# vca.net
KiCad netlist of a schematic drawn in EAGLE
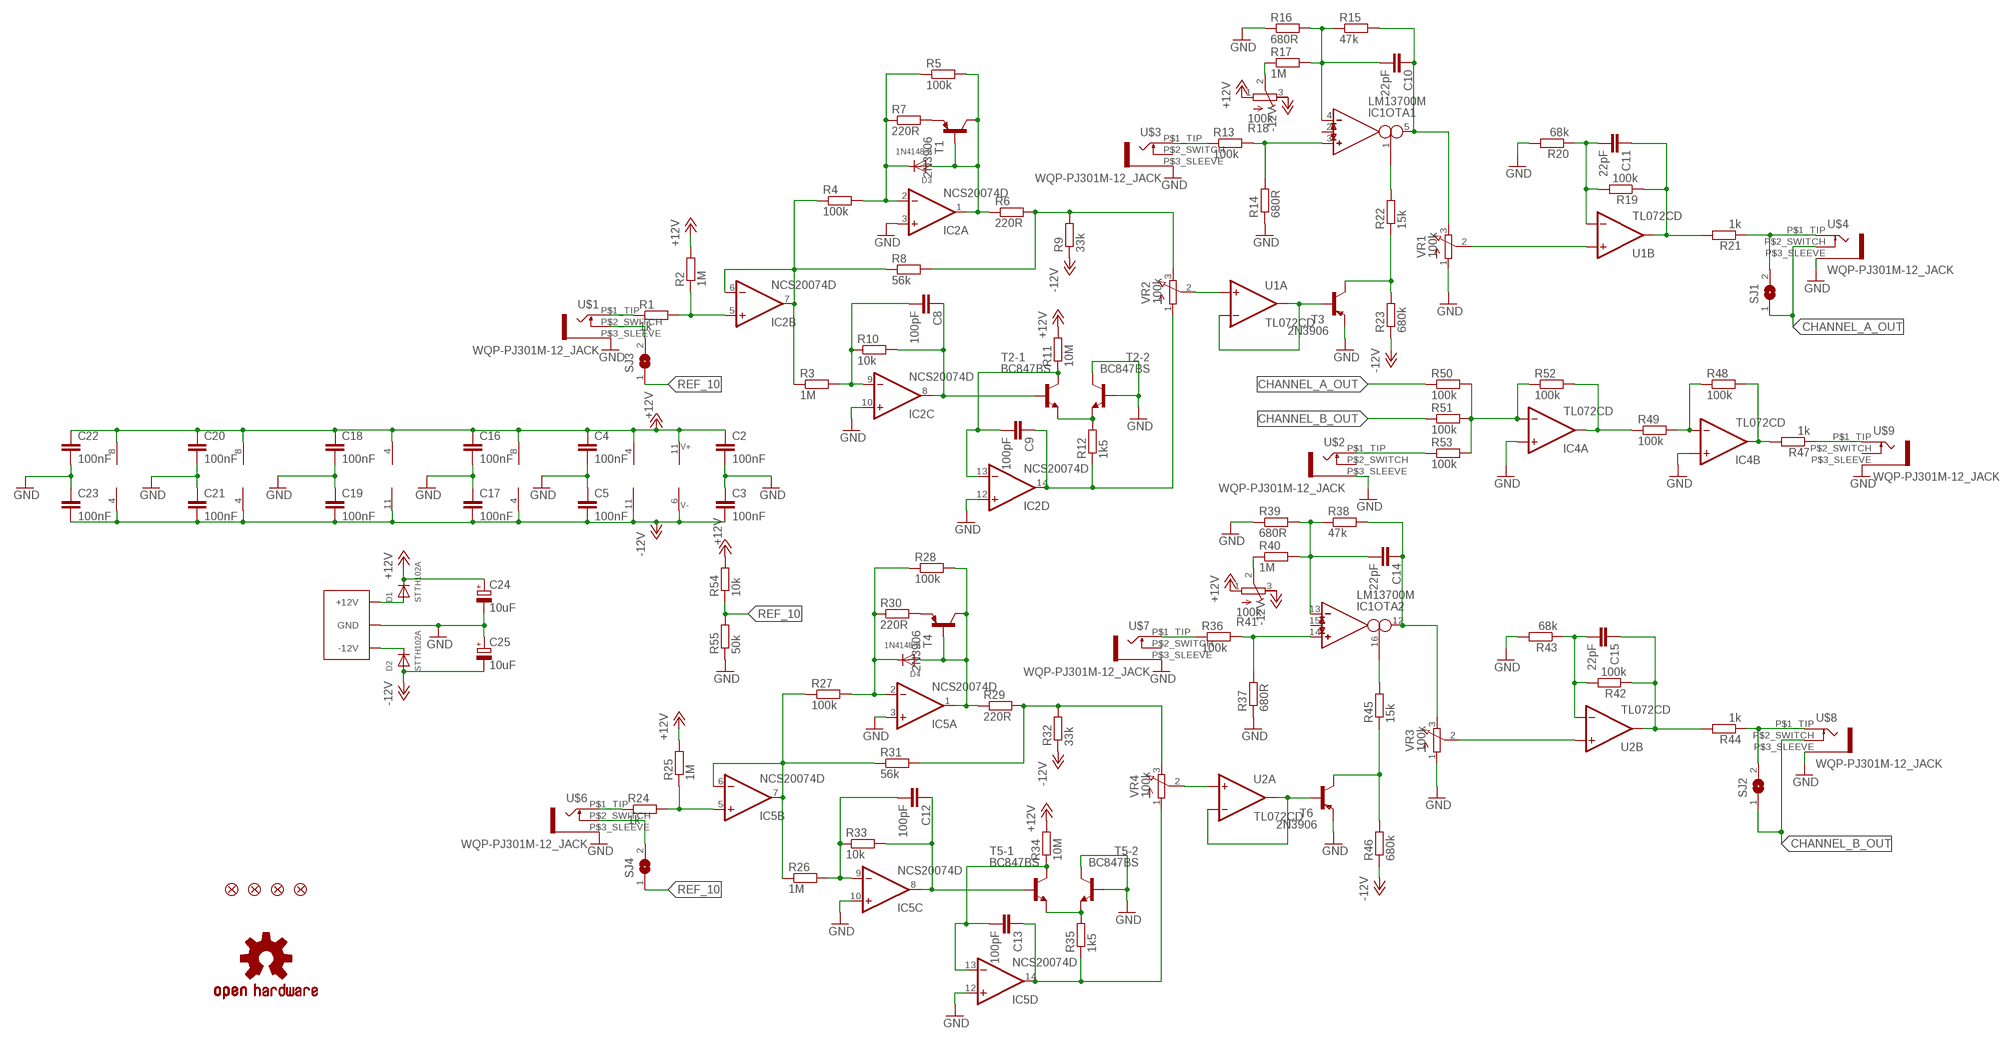
[diagram p0: schematic, sheet 1]

(export (version "E")
  (design (tool "Eeschema 10.0.6"))
  (components
    (comp (ref "C1")
      (value "EURO_POWER_LOCKFAT-LOCK")
      (footprint "eagle-import:EURO_PWR_HEADER_LOCK")
      (libsource (lib "eagle-import") (part "EURO_POWER_LOCKFAT-LOCK"))
    )
    (comp (ref "C2")
      (value "100nF")
      (footprint "eagle-import:C0402")
      (libsource (lib "eagle-import") (part "C-EUC0402"))
    )
    (comp (ref "C3")
      (value "100nF")
      (footprint "eagle-import:C0402")
      (libsource (lib "eagle-import") (part "C-EUC0402"))
    )
    (comp (ref "C4")
      (value "100nF")
      (footprint "eagle-import:C0402")
      (libsource (lib "eagle-import") (part "C-EUC0402"))
    )
    (comp (ref "C5")
      (value "100nF")
      (footprint "eagle-import:C0402")
      (libsource (lib "eagle-import") (part "C-EUC0402"))
    )
    (comp (ref "C8")
      (value "100pF")
      (footprint "eagle-import:C0402")
      (libsource (lib "eagle-import") (part "C-EUC0402"))
    )
    (comp (ref "C9")
      (value "100pF")
      (footprint "eagle-import:C0402")
      (libsource (lib "eagle-import") (part "C-EUC0402"))
    )
    (comp (ref "C10")
      (value "22pF")
      (footprint "eagle-import:C0402")
      (libsource (lib "eagle-import") (part "C-EUC0402"))
    )
    (comp (ref "C11")
      (value "22pF")
      (footprint "eagle-import:C0402")
      (libsource (lib "eagle-import") (part "C-EUC0402"))
    )
    (comp (ref "C12")
      (value "100pF")
      (footprint "eagle-import:C0402")
      (libsource (lib "eagle-import") (part "C-EUC0402"))
    )
    (comp (ref "C13")
      (value "100pF")
      (footprint "eagle-import:C0402")
      (libsource (lib "eagle-import") (part "C-EUC0402"))
    )
    (comp (ref "C14")
      (value "22pF")
      (footprint "eagle-import:C0402")
      (libsource (lib "eagle-import") (part "C-EUC0402"))
    )
    (comp (ref "C15")
      (value "22pF")
      (footprint "eagle-import:C0402")
      (libsource (lib "eagle-import") (part "C-EUC0402"))
    )
    (comp (ref "C16")
      (value "100nF")
      (footprint "eagle-import:C0402")
      (libsource (lib "eagle-import") (part "C-EUC0402"))
    )
    (comp (ref "C17")
      (value "100nF")
      (footprint "eagle-import:C0402")
      (libsource (lib "eagle-import") (part "C-EUC0402"))
    )
    (comp (ref "C18")
      (value "100nF")
      (footprint "eagle-import:C0402")
      (libsource (lib "eagle-import") (part "C-EUC0402"))
    )
    (comp (ref "C19")
      (value "100nF")
      (footprint "eagle-import:C0402")
      (libsource (lib "eagle-import") (part "C-EUC0402"))
    )
    (comp (ref "C20")
      (value "100nF")
      (footprint "eagle-import:C0402")
      (libsource (lib "eagle-import") (part "C-EUC0402"))
    )
    (comp (ref "C21")
      (value "100nF")
      (footprint "eagle-import:C0402")
      (libsource (lib "eagle-import") (part "C-EUC0402"))
    )
    (comp (ref "C22")
      (value "100nF")
      (footprint "eagle-import:C0402")
      (libsource (lib "eagle-import") (part "C-EUC0402"))
    )
    (comp (ref "C23")
      (value "100nF")
      (footprint "eagle-import:C0402")
      (libsource (lib "eagle-import") (part "C-EUC0402"))
    )
    (comp (ref "C24")
      (value "10uF")
      (footprint "eagle-import:A_3216-18W")
      (libsource (lib "eagle-import") (part "CPOL-EUA/3216-18W"))
    )
    (comp (ref "C25")
      (value "10uF")
      (footprint "eagle-import:A_3216-18W")
      (libsource (lib "eagle-import") (part "CPOL-EUA/3216-18W"))
    )
    (comp (ref "D1")
      (value "STTH102A")
      (footprint "eagle-import:SMADIODE")
      (libsource (lib "eagle-import") (part "DIODESMA"))
    )
    (comp (ref "D2")
      (value "STTH102A")
      (footprint "eagle-import:SMADIODE")
      (libsource (lib "eagle-import") (part "DIODESMA"))
    )
    (comp (ref "D3")
      (value "1N4148-2")
      (footprint "eagle-import:SOD-123")
      (libsource (lib "eagle-import") (part "DIODESOD-123"))
    )
    (comp (ref "D4")
      (value "1N4148-2")
      (footprint "eagle-import:SOD-123")
      (libsource (lib "eagle-import") (part "DIODESOD-123"))
    )
    (comp (ref "FD1")
      (value "FIDUCIAL1X2")
      (footprint "eagle-import:FIDUCIAL-1X2")
      (libsource (lib "eagle-import") (part "FIDUCIAL1X2"))
    )
    (comp (ref "FD2")
      (value "FIDUCIAL1X2")
      (footprint "eagle-import:FIDUCIAL-1X2")
      (libsource (lib "eagle-import") (part "FIDUCIAL1X2"))
    )
    (comp (ref "FD3")
      (value "FIDUCIAL1X2")
      (footprint "eagle-import:FIDUCIAL-1X2")
      (libsource (lib "eagle-import") (part "FIDUCIAL1X2"))
    )
    (comp (ref "FD4")
      (value "FIDUCIAL1X2")
      (footprint "eagle-import:FIDUCIAL-1X2")
      (libsource (lib "eagle-import") (part "FIDUCIAL1X2"))
    )
    (comp (ref "IC1")
      (value "LM13700M")
      (footprint "eagle-import:SO16")
      (libsource (lib "eagle-import") (part "LM13700M"))
    )
    (comp (ref "IC2")
      (value "NCS20074D")
      (footprint "eagle-import:SO14")
      (libsource (lib "eagle-import") (part "NCS20074D"))
    )
    (comp (ref "IC4")
      (value "TL072CD")
      (footprint "eagle-import:SOIC8")
      (libsource (lib "eagle-import") (part "TL072DC"))
    )
    (comp (ref "IC5")
      (value "NCS20074D")
      (footprint "eagle-import:SO14")
      (libsource (lib "eagle-import") (part "NCS20074D"))
    )
    (comp (ref "LOGO1")
      (value "OSHW-LOGOM")
      (footprint "eagle-import:OSHW-LOGO-M")
      (libsource (lib "eagle-import") (part "OSHW-LOGOM"))
    )
    (comp (ref "R1")
      (value "1k")
      (footprint "eagle-import:R0402")
      (libsource (lib "eagle-import") (part "R-EU_R0402"))
    )
    (comp (ref "R2")
      (value "1M")
      (footprint "eagle-import:R0402")
      (libsource (lib "eagle-import") (part "R-EU_R0402"))
    )
    (comp (ref "R3")
      (value "1M")
      (footprint "eagle-import:R0402")
      (libsource (lib "eagle-import") (part "R-EU_R0402"))
    )
    (comp (ref "R4")
      (value "100k")
      (footprint "eagle-import:R0402")
      (libsource (lib "eagle-import") (part "R-EU_R0402"))
    )
    (comp (ref "R5")
      (value "100k")
      (footprint "eagle-import:R0402")
      (libsource (lib "eagle-import") (part "R-EU_R0402"))
    )
    (comp (ref "R6")
      (value "220R")
      (footprint "eagle-import:R0402")
      (libsource (lib "eagle-import") (part "R-EU_R0402"))
    )
    (comp (ref "R7")
      (value "220R")
      (footprint "eagle-import:R0402")
      (libsource (lib "eagle-import") (part "R-EU_R0402"))
    )
    (comp (ref "R8")
      (value "56k")
      (footprint "eagle-import:R0402")
      (libsource (lib "eagle-import") (part "R-EU_R0402"))
    )
    (comp (ref "R9")
      (value "33k")
      (footprint "eagle-import:R0402")
      (libsource (lib "eagle-import") (part "R-EU_R0402"))
    )
    (comp (ref "R10")
      (value "10k")
      (footprint "eagle-import:R0402")
      (libsource (lib "eagle-import") (part "R-EU_R0402"))
    )
    (comp (ref "R11")
      (value "10M")
      (footprint "eagle-import:R0402")
      (libsource (lib "eagle-import") (part "R-EU_R0402"))
    )
    (comp (ref "R12")
      (value "1k5")
      (footprint "eagle-import:R0402")
      (libsource (lib "eagle-import") (part "R-EU_R0402"))
    )
    (comp (ref "R13")
      (value "100k")
      (footprint "eagle-import:R0402")
      (libsource (lib "eagle-import") (part "R-EU_R0402"))
    )
    (comp (ref "R14")
      (value "680R")
      (footprint "eagle-import:R0402")
      (libsource (lib "eagle-import") (part "R-EU_R0402"))
    )
    (comp (ref "R15")
      (value "47k")
      (footprint "eagle-import:R0402")
      (libsource (lib "eagle-import") (part "R-EU_R0402"))
    )
    (comp (ref "R16")
      (value "680R")
      (footprint "eagle-import:R0402")
      (libsource (lib "eagle-import") (part "R-EU_R0402"))
    )
    (comp (ref "R17")
      (value "1M")
      (footprint "eagle-import:R0402")
      (libsource (lib "eagle-import") (part "R-EU_R0402"))
    )
    (comp (ref "R18")
      (value "100k")
      (footprint "eagle-import:RTRIM64W")
      (libsource (lib "eagle-import") (part "R-TRIMM64W"))
    )
    (comp (ref "R19")
      (value "100k")
      (footprint "eagle-import:R0402")
      (libsource (lib "eagle-import") (part "R-EU_R0402"))
    )
    (comp (ref "R20")
      (value "68k")
      (footprint "eagle-import:R0402")
      (libsource (lib "eagle-import") (part "R-EU_R0402"))
    )
    (comp (ref "R21")
      (value "1k")
      (footprint "eagle-import:R0402")
      (libsource (lib "eagle-import") (part "R-EU_R0402"))
    )
    (comp (ref "R22")
      (value "15k")
      (footprint "eagle-import:R0402")
      (libsource (lib "eagle-import") (part "R-EU_R0402"))
    )
    (comp (ref "R23")
      (value "680k")
      (footprint "eagle-import:R0402")
      (libsource (lib "eagle-import") (part "R-EU_R0402"))
    )
    (comp (ref "R24")
      (value "1k")
      (footprint "eagle-import:R0402")
      (libsource (lib "eagle-import") (part "R-EU_R0402"))
    )
    (comp (ref "R25")
      (value "1M")
      (footprint "eagle-import:R0402")
      (libsource (lib "eagle-import") (part "R-EU_R0402"))
    )
    (comp (ref "R26")
      (value "1M")
      (footprint "eagle-import:R0402")
      (libsource (lib "eagle-import") (part "R-EU_R0402"))
    )
    (comp (ref "R27")
      (value "100k")
      (footprint "eagle-import:R0402")
      (libsource (lib "eagle-import") (part "R-EU_R0402"))
    )
    (comp (ref "R28")
      (value "100k")
      (footprint "eagle-import:R0402")
      (libsource (lib "eagle-import") (part "R-EU_R0402"))
    )
    (comp (ref "R29")
      (value "220R")
      (footprint "eagle-import:R0402")
      (libsource (lib "eagle-import") (part "R-EU_R0402"))
    )
    (comp (ref "R30")
      (value "220R")
      (footprint "eagle-import:R0402")
      (libsource (lib "eagle-import") (part "R-EU_R0402"))
    )
    (comp (ref "R31")
      (value "56k")
      (footprint "eagle-import:R0402")
      (libsource (lib "eagle-import") (part "R-EU_R0402"))
    )
    (comp (ref "R32")
      (value "33k")
      (footprint "eagle-import:R0402")
      (libsource (lib "eagle-import") (part "R-EU_R0402"))
    )
    (comp (ref "R33")
      (value "10k")
      (footprint "eagle-import:R0402")
      (libsource (lib "eagle-import") (part "R-EU_R0402"))
    )
    (comp (ref "R34")
      (value "10M")
      (footprint "eagle-import:R0402")
      (libsource (lib "eagle-import") (part "R-EU_R0402"))
    )
    (comp (ref "R35")
      (value "1k5")
      (footprint "eagle-import:R0402")
      (libsource (lib "eagle-import") (part "R-EU_R0402"))
    )
    (comp (ref "R36")
      (value "100k")
      (footprint "eagle-import:R0402")
      (libsource (lib "eagle-import") (part "R-EU_R0402"))
    )
    (comp (ref "R37")
      (value "680R")
      (footprint "eagle-import:R0402")
      (libsource (lib "eagle-import") (part "R-EU_R0402"))
    )
    (comp (ref "R38")
      (value "47k")
      (footprint "eagle-import:R0402")
      (libsource (lib "eagle-import") (part "R-EU_R0402"))
    )
    (comp (ref "R39")
      (value "680R")
      (footprint "eagle-import:R0402")
      (libsource (lib "eagle-import") (part "R-EU_R0402"))
    )
    (comp (ref "R40")
      (value "1M")
      (footprint "eagle-import:R0402")
      (libsource (lib "eagle-import") (part "R-EU_R0402"))
    )
    (comp (ref "R41")
      (value "100k")
      (footprint "eagle-import:RTRIM64W")
      (libsource (lib "eagle-import") (part "R-TRIMM64W"))
    )
    (comp (ref "R42")
      (value "100k")
      (footprint "eagle-import:R0402")
      (libsource (lib "eagle-import") (part "R-EU_R0402"))
    )
    (comp (ref "R43")
      (value "68k")
      (footprint "eagle-import:R0402")
      (libsource (lib "eagle-import") (part "R-EU_R0402"))
    )
    (comp (ref "R44")
      (value "1k")
      (footprint "eagle-import:R0402")
      (libsource (lib "eagle-import") (part "R-EU_R0402"))
    )
    (comp (ref "R45")
      (value "15k")
      (footprint "eagle-import:R0402")
      (libsource (lib "eagle-import") (part "R-EU_R0402"))
    )
    (comp (ref "R46")
      (value "680k")
      (footprint "eagle-import:R0402")
      (libsource (lib "eagle-import") (part "R-EU_R0402"))
    )
    (comp (ref "R47")
      (value "1k")
      (footprint "eagle-import:R0402")
      (libsource (lib "eagle-import") (part "R-EU_R0402"))
    )
    (comp (ref "R48")
      (value "100k")
      (footprint "eagle-import:R0402")
      (libsource (lib "eagle-import") (part "R-EU_R0402"))
    )
    (comp (ref "R49")
      (value "100k")
      (footprint "eagle-import:R0402")
      (libsource (lib "eagle-import") (part "R-EU_R0402"))
    )
    (comp (ref "R50")
      (value "100k")
      (footprint "eagle-import:R0402")
      (libsource (lib "eagle-import") (part "R-EU_R0402"))
    )
    (comp (ref "R51")
      (value "100k")
      (footprint "eagle-import:R0402")
      (libsource (lib "eagle-import") (part "R-EU_R0402"))
    )
    (comp (ref "R52")
      (value "100k")
      (footprint "eagle-import:R0402")
      (libsource (lib "eagle-import") (part "R-EU_R0402"))
    )
    (comp (ref "R53")
      (value "100k")
      (footprint "eagle-import:R0402")
      (libsource (lib "eagle-import") (part "R-EU_R0402"))
    )
    (comp (ref "R54")
      (value "10k")
      (footprint "eagle-import:R0402")
      (libsource (lib "eagle-import") (part "R-EU_R0402"))
    )
    (comp (ref "R55")
      (value "50k")
      (footprint "eagle-import:R0402")
      (libsource (lib "eagle-import") (part "R-EU_R0402"))
    )
    (comp (ref "SJ1") (value "SJ") (footprint "eagle-import:SJ") (libsource (lib "eagle-import") (part "SJ")))
    (comp (ref "SJ2") (value "SJ") (footprint "eagle-import:SJ") (libsource (lib "eagle-import") (part "SJ")))
    (comp (ref "SJ3") (value "SJ") (footprint "eagle-import:SJ") (libsource (lib "eagle-import") (part "SJ")))
    (comp (ref "SJ4") (value "SJ") (footprint "eagle-import:SJ") (libsource (lib "eagle-import") (part "SJ")))
    (comp (ref "T1")
      (value "2N3906")
      (footprint "eagle-import:SOT23-BEC")
      (libsource (lib "eagle-import") (part "-PNP-SOT23-BECMMBT3906LT1"))
    )
    (comp (ref "T2")
      (value "BC847BS")
      (footprint "eagle-import:SOT363")
      (libsource (lib "eagle-import") (part "BC847BS"))
    )
    (comp (ref "T3")
      (value "2N3906")
      (footprint "eagle-import:SOT23-BEC")
      (libsource (lib "eagle-import") (part "-PNP-SOT23-BECMMBT3906LT1"))
    )
    (comp (ref "T4")
      (value "2N3906")
      (footprint "eagle-import:SOT23-BEC")
      (libsource (lib "eagle-import") (part "-PNP-SOT23-BECMMBT3906LT1"))
    )
    (comp (ref "T5")
      (value "BC847BS")
      (footprint "eagle-import:SOT363")
      (libsource (lib "eagle-import") (part "BC847BS"))
    )
    (comp (ref "T6")
      (value "2N3906")
      (footprint "eagle-import:SOT23-BEC")
      (libsource (lib "eagle-import") (part "-PNP-SOT23-BECMMBT3906LT1"))
    )
    (comp (ref "U$1")
      (value "WQP-PJ301M-12_JACK")
      (footprint "eagle-import:WQP-PJ301M-12_JACK")
      (libsource (lib "eagle-import") (part "WQP-PJ301M-12_JACK"))
    )
    (comp (ref "U$2")
      (value "WQP-PJ301M-12_JACK")
      (footprint "eagle-import:WQP-PJ301M-12_JACK")
      (libsource (lib "eagle-import") (part "WQP-PJ301M-12_JACK"))
    )
    (comp (ref "U$3")
      (value "WQP-PJ301M-12_JACK")
      (footprint "eagle-import:WQP-PJ301M-12_JACK")
      (libsource (lib "eagle-import") (part "WQP-PJ301M-12_JACK"))
    )
    (comp (ref "U$4")
      (value "WQP-PJ301M-12_JACK")
      (footprint "eagle-import:WQP-PJ301M-12_JACK")
      (libsource (lib "eagle-import") (part "WQP-PJ301M-12_JACK"))
    )
    (comp (ref "U$6")
      (value "WQP-PJ301M-12_JACK")
      (footprint "eagle-import:WQP-PJ301M-12_JACK")
      (libsource (lib "eagle-import") (part "WQP-PJ301M-12_JACK"))
    )
    (comp (ref "U$7")
      (value "WQP-PJ301M-12_JACK")
      (footprint "eagle-import:WQP-PJ301M-12_JACK")
      (libsource (lib "eagle-import") (part "WQP-PJ301M-12_JACK"))
    )
    (comp (ref "U$8")
      (value "WQP-PJ301M-12_JACK")
      (footprint "eagle-import:WQP-PJ301M-12_JACK")
      (libsource (lib "eagle-import") (part "WQP-PJ301M-12_JACK"))
    )
    (comp (ref "U$9")
      (value "WQP-PJ301M-12_JACK")
      (footprint "eagle-import:WQP-PJ301M-12_JACK")
      (libsource (lib "eagle-import") (part "WQP-PJ301M-12_JACK"))
    )
    (comp (ref "U1")
      (value "TL072CD")
      (footprint "eagle-import:SOIC8")
      (libsource (lib "eagle-import") (part "TL072DC"))
    )
    (comp (ref "U2")
      (value "TL072CD")
      (footprint "eagle-import:SOIC8")
      (libsource (lib "eagle-import") (part "TL072DC"))
    )
    (comp (ref "VR1")
      (value "100k")
      (footprint "eagle-import:9MM_SNAP-IN_POT")
      (libsource (lib "eagle-import") (part "9MM_SNAP-IN_POT_"))
    )
    (comp (ref "VR2")
      (value "100k")
      (footprint "eagle-import:9MM_SNAP-IN_POT")
      (libsource (lib "eagle-import") (part "9MM_SNAP-IN_POT_"))
    )
    (comp (ref "VR3")
      (value "100k")
      (footprint "eagle-import:9MM_SNAP-IN_POT")
      (libsource (lib "eagle-import") (part "9MM_SNAP-IN_POT_"))
    )
    (comp (ref "VR4")
      (value "100k")
      (footprint "eagle-import:9MM_SNAP-IN_POT")
      (libsource (lib "eagle-import") (part "9MM_SNAP-IN_POT_"))
    )
  )
  (nets
    (net (code "1") (name "+12V") (class "Default")
      (node (ref "C16") (pin "1") (pinfunction "1_1") (pintype "passive"))
      (node (ref "C18") (pin "1") (pinfunction "1_1") (pintype "passive"))
      (node (ref "C2") (pin "1") (pinfunction "1_1") (pintype "passive"))
      (node (ref "C20") (pin "1") (pinfunction "1_1") (pintype "passive"))
      (node (ref "C22") (pin "1") (pinfunction "1_1") (pintype "passive"))
      (node (ref "C24") (pin "+") (pinfunction "+_+") (pintype "passive"))
      (node (ref "C4") (pin "1") (pinfunction "1_1") (pintype "passive"))
      (node (ref "D1") (pin "C") (pinfunction "C_C") (pintype "passive"))
      (node (ref "IC1") (pin "11") (pinfunction "V+_11") (pintype "power_in"))
      (node (ref "IC2") (pin "4") (pinfunction "V+_4") (pintype "power_in"))
      (node (ref "IC4") (pin "8") (pinfunction "V+_8") (pintype "power_in"))
      (node (ref "IC5") (pin "4") (pinfunction "V+_4") (pintype "power_in"))
      (node (ref "R11") (pin "2") (pinfunction "2_2") (pintype "passive"))
      (node (ref "R18") (pin "1") (pinfunction "A_1") (pintype "passive"))
      (node (ref "R2") (pin "2") (pinfunction "2_2") (pintype "passive"))
      (node (ref "R25") (pin "2") (pinfunction "2_2") (pintype "passive"))
      (node (ref "R34") (pin "2") (pinfunction "2_2") (pintype "passive"))
      (node (ref "R41") (pin "1") (pinfunction "A_1") (pintype "passive"))
      (node (ref "R54") (pin "2") (pinfunction "2_2") (pintype "passive"))
      (node (ref "U1") (pin "8") (pinfunction "V+_8") (pintype "power_in"))
      (node (ref "U2") (pin "8") (pinfunction "V+_8") (pintype "power_in"))
    )
    (net (code "2") (name "-12V") (class "Default")
      (node (ref "C17") (pin "2") (pinfunction "2_2") (pintype "passive"))
      (node (ref "C19") (pin "2") (pinfunction "2_2") (pintype "passive"))
      (node (ref "C21") (pin "2") (pinfunction "2_2") (pintype "passive"))
      (node (ref "C23") (pin "2") (pinfunction "2_2") (pintype "passive"))
      (node (ref "C25") (pin "-") (pinfunction "-_-") (pintype "passive"))
      (node (ref "C3") (pin "2") (pinfunction "2_2") (pintype "passive"))
      (node (ref "C5") (pin "2") (pinfunction "2_2") (pintype "passive"))
      (node (ref "D2") (pin "A") (pinfunction "A_A") (pintype "passive"))
      (node (ref "IC1") (pin "6") (pinfunction "V-_6") (pintype "power_in"))
      (node (ref "IC2") (pin "11") (pinfunction "V-_11") (pintype "power_in"))
      (node (ref "IC4") (pin "4") (pinfunction "V-_4") (pintype "power_in"))
      (node (ref "IC5") (pin "11") (pinfunction "V-_11") (pintype "power_in"))
      (node (ref "R18") (pin "3") (pinfunction "E_3") (pintype "passive"))
      (node (ref "R23") (pin "1") (pinfunction "1_1") (pintype "passive"))
      (node (ref "R32") (pin "1") (pinfunction "1_1") (pintype "passive"))
      (node (ref "R41") (pin "3") (pinfunction "E_3") (pintype "passive"))
      (node (ref "R46") (pin "1") (pinfunction "1_1") (pintype "passive"))
      (node (ref "R9") (pin "1") (pinfunction "1_1") (pintype "passive"))
      (node (ref "U1") (pin "4") (pinfunction "V-_4") (pintype "power_in"))
      (node (ref "U2") (pin "4") (pinfunction "V-_4") (pintype "power_in"))
    )
    (net (code "3") (name "CHANNEL_A_OUT") (class "Default")
      (node (ref "R50") (pin "1") (pinfunction "1_1") (pintype "passive"))
      (node (ref "SJ1") (pin "1") (pinfunction "1_1") (pintype "passive"))
      (node (ref "U$4") (pin "P$2_SWITCH") (pinfunction "3_P$2_SWITCH") (pintype "passive"))
    )
    (net (code "4") (name "CHANNEL_B_OUT") (class "Default")
      (node (ref "R51") (pin "1") (pinfunction "1_1") (pintype "passive"))
      (node (ref "SJ2") (pin "1") (pinfunction "1_1") (pintype "passive"))
      (node (ref "U$8") (pin "P$2_SWITCH") (pinfunction "3_P$2_SWITCH") (pintype "passive"))
    )
    (net (code "5") (name "GND") (class "Default")
      (node (ref "C1") (pin "GND1") (pinfunction "GND_GND1") (pintype "bidirectional"))
      (node (ref "C1") (pin "GND2") (pinfunction "GND_GND2") (pintype "bidirectional"))
      (node (ref "C1") (pin "GND3") (pinfunction "GND_GND3") (pintype "bidirectional"))
      (node (ref "C1") (pin "GND4") (pinfunction "GND_GND4") (pintype "bidirectional"))
      (node (ref "C1") (pin "GND5") (pinfunction "GND_GND5") (pintype "bidirectional"))
      (node (ref "C1") (pin "GND6") (pinfunction "GND_GND6") (pintype "bidirectional"))
      (node (ref "C16") (pin "2") (pinfunction "2_2") (pintype "passive"))
      (node (ref "C17") (pin "1") (pinfunction "1_1") (pintype "passive"))
      (node (ref "C18") (pin "2") (pinfunction "2_2") (pintype "passive"))
      (node (ref "C19") (pin "1") (pinfunction "1_1") (pintype "passive"))
      (node (ref "C2") (pin "2") (pinfunction "2_2") (pintype "passive"))
      (node (ref "C20") (pin "2") (pinfunction "2_2") (pintype "passive"))
      (node (ref "C21") (pin "1") (pinfunction "1_1") (pintype "passive"))
      (node (ref "C22") (pin "2") (pinfunction "2_2") (pintype "passive"))
      (node (ref "C23") (pin "1") (pinfunction "1_1") (pintype "passive"))
      (node (ref "C24") (pin "-") (pinfunction "-_-") (pintype "passive"))
      (node (ref "C25") (pin "+") (pinfunction "+_+") (pintype "passive"))
      (node (ref "C3") (pin "1") (pinfunction "1_1") (pintype "passive"))
      (node (ref "C4") (pin "2") (pinfunction "2_2") (pintype "passive"))
      (node (ref "C5") (pin "1") (pinfunction "1_1") (pintype "passive"))
      (node (ref "IC2") (pin "10") (pinfunction "+IN_10") (pintype "input"))
      (node (ref "IC2") (pin "12") (pinfunction "+IN_12") (pintype "input"))
      (node (ref "IC2") (pin "3") (pinfunction "+IN_3") (pintype "input"))
      (node (ref "IC4") (pin "3") (pinfunction "+IN_3") (pintype "input"))
      (node (ref "IC4") (pin "5") (pinfunction "+IN_5") (pintype "input"))
      (node (ref "IC5") (pin "10") (pinfunction "+IN_10") (pintype "input"))
      (node (ref "IC5") (pin "12") (pinfunction "+IN_12") (pintype "input"))
      (node (ref "IC5") (pin "3") (pinfunction "+IN_3") (pintype "input"))
      (node (ref "R14") (pin "1") (pinfunction "1_1") (pintype "passive"))
      (node (ref "R16") (pin "1") (pinfunction "1_1") (pintype "passive"))
      (node (ref "R20") (pin "2") (pinfunction "2_2") (pintype "passive"))
      (node (ref "R37") (pin "1") (pinfunction "1_1") (pintype "passive"))
      (node (ref "R39") (pin "1") (pinfunction "1_1") (pintype "passive"))
      (node (ref "R43") (pin "2") (pinfunction "2_2") (pintype "passive"))
      (node (ref "R55") (pin "1") (pinfunction "1_1") (pintype "passive"))
      (node (ref "T2") (pin "3") (pinfunction "C_3") (pintype "passive"))
      (node (ref "T2") (pin "5") (pinfunction "B_5") (pintype "passive"))
      (node (ref "T3") (pin "E") (pinfunction "E_E") (pintype "passive"))
      (node (ref "T5") (pin "3") (pinfunction "C_3") (pintype "passive"))
      (node (ref "T5") (pin "5") (pinfunction "B_5") (pintype "passive"))
      (node (ref "T6") (pin "E") (pinfunction "E_E") (pintype "passive"))
      (node (ref "U$1") (pin "P$3_SLEEVE") (pinfunction "1_P$3_SLEEVE") (pintype "passive"))
      (node (ref "U$2") (pin "P$3_SLEEVE") (pinfunction "1_P$3_SLEEVE") (pintype "passive"))
      (node (ref "U$3") (pin "P$3_SLEEVE") (pinfunction "1_P$3_SLEEVE") (pintype "passive"))
      (node (ref "U$4") (pin "P$3_SLEEVE") (pinfunction "1_P$3_SLEEVE") (pintype "passive"))
      (node (ref "U$6") (pin "P$3_SLEEVE") (pinfunction "1_P$3_SLEEVE") (pintype "passive"))
      (node (ref "U$7") (pin "P$3_SLEEVE") (pinfunction "1_P$3_SLEEVE") (pintype "passive"))
      (node (ref "U$8") (pin "P$3_SLEEVE") (pinfunction "1_P$3_SLEEVE") (pintype "passive"))
      (node (ref "U$9") (pin "P$3_SLEEVE") (pinfunction "1_P$3_SLEEVE") (pintype "passive"))
      (node (ref "VR1") (pin "1") (pinfunction "A_1") (pintype "passive"))
      (node (ref "VR3") (pin "1") (pinfunction "A_1") (pintype "passive"))
    )
    (net (code "6") (name "Net-(C1-+12V-PadPOS1)") (class "Default")
      (node (ref "C1") (pin "POS1") (pinfunction "+12V_POS1") (pintype "bidirectional"))
      (node (ref "C1") (pin "POS2") (pinfunction "+12V_POS2") (pintype "bidirectional"))
      (node (ref "D1") (pin "A") (pinfunction "A_A") (pintype "passive"))
    )
    (net (code "7") (name "Net-(C1--12V-PadNEG1)") (class "Default")
      (node (ref "C1") (pin "NEG1") (pinfunction "-12V_NEG1") (pintype "bidirectional"))
      (node (ref "C1") (pin "NEG2") (pinfunction "-12V_NEG2") (pintype "bidirectional"))
      (node (ref "D2") (pin "C") (pinfunction "C_C") (pintype "passive"))
    )
    (net (code "8") (name "Net-(IC1C-IN_N)") (class "Default")
      (node (ref "C10") (pin "2") (pinfunction "2_2") (pintype "passive"))
      (node (ref "IC1") (pin "4") (pinfunction "IN_N_4") (pintype "input"))
      (node (ref "R15") (pin "1") (pinfunction "1_1") (pintype "passive"))
      (node (ref "R16") (pin "2") (pinfunction "2_2") (pintype "passive"))
      (node (ref "R17") (pin "2") (pinfunction "2_2") (pintype "passive"))
    )
    (net (code "9") (name "Net-(IC1C-IN_P)") (class "Default")
      (node (ref "IC1") (pin "3") (pinfunction "IN_P_3") (pintype "input"))
      (node (ref "R13") (pin "2") (pinfunction "2_2") (pintype "passive"))
      (node (ref "R14") (pin "2") (pinfunction "2_2") (pintype "passive"))
    )
    (net (code "10") (name "Net-(IC1C-I_BIAS)") (class "Default")
      (node (ref "IC1") (pin "1") (pinfunction "I_BIAS_1") (pintype "input"))
      (node (ref "R22") (pin "2") (pinfunction "2_2") (pintype "passive"))
    )
    (net (code "11") (name "Net-(IC1C-OUT)") (class "Default")
      (node (ref "C10") (pin "1") (pinfunction "1_1") (pintype "passive"))
      (node (ref "IC1") (pin "5") (pinfunction "OUT_5") (pintype "output"))
      (node (ref "R15") (pin "2") (pinfunction "2_2") (pintype "passive"))
      (node (ref "VR1") (pin "3") (pinfunction "E_3") (pintype "passive"))
    )
    (net (code "12") (name "Net-(IC1D-IN_N)") (class "Default")
      (node (ref "C14") (pin "2") (pinfunction "2_2") (pintype "passive"))
      (node (ref "IC1") (pin "13") (pinfunction "IN_N_13") (pintype "input"))
      (node (ref "R38") (pin "1") (pinfunction "1_1") (pintype "passive"))
      (node (ref "R39") (pin "2") (pinfunction "2_2") (pintype "passive"))
      (node (ref "R40") (pin "2") (pinfunction "2_2") (pintype "passive"))
    )
    (net (code "13") (name "Net-(IC1D-IN_P)") (class "Default")
      (node (ref "IC1") (pin "14") (pinfunction "IN_P_14") (pintype "input"))
      (node (ref "R36") (pin "2") (pinfunction "2_2") (pintype "passive"))
      (node (ref "R37") (pin "2") (pinfunction "2_2") (pintype "passive"))
    )
    (net (code "14") (name "Net-(IC1D-I_BIAS)") (class "Default")
      (node (ref "IC1") (pin "16") (pinfunction "I_BIAS_16") (pintype "input"))
      (node (ref "R45") (pin "2") (pinfunction "2_2") (pintype "passive"))
    )
    (net (code "15") (name "Net-(IC1D-OUT)") (class "Default")
      (node (ref "C14") (pin "1") (pinfunction "1_1") (pintype "passive"))
      (node (ref "IC1") (pin "12") (pinfunction "OUT_12") (pintype "output"))
      (node (ref "R38") (pin "2") (pinfunction "2_2") (pintype "passive"))
      (node (ref "VR3") (pin "3") (pinfunction "E_3") (pintype "passive"))
    )
    (net (code "16") (name "Net-(IC2A--IN)") (class "Default")
      (node (ref "D3") (pin "C") (pinfunction "C_C") (pintype "passive"))
      (node (ref "IC2") (pin "2") (pinfunction "-IN_2") (pintype "input"))
      (node (ref "R4") (pin "2") (pinfunction "2_2") (pintype "passive"))
      (node (ref "R5") (pin "1") (pinfunction "1_1") (pintype "passive"))
      (node (ref "R7") (pin "1") (pinfunction "1_1") (pintype "passive"))
    )
    (net (code "17") (name "Net-(IC2A-OUT)") (class "Default")
      (node (ref "D3") (pin "A") (pinfunction "A_A") (pintype "passive"))
      (node (ref "IC2") (pin "1") (pinfunction "OUT_1") (pintype "output"))
      (node (ref "R5") (pin "2") (pinfunction "2_2") (pintype "passive"))
      (node (ref "R6") (pin "1") (pinfunction "1_1") (pintype "passive"))
      (node (ref "T1") (pin "B") (pinfunction "B_B") (pintype "passive"))
      (node (ref "T1") (pin "C") (pinfunction "C_C") (pintype "passive"))
    )
    (net (code "18") (name "Net-(IC2B-+IN)") (class "Default")
      (node (ref "IC2") (pin "5") (pinfunction "+IN_5") (pintype "input"))
      (node (ref "R1") (pin "2") (pinfunction "2_2") (pintype "passive"))
      (node (ref "R2") (pin "1") (pinfunction "1_1") (pintype "passive"))
    )
    (net (code "19") (name "Net-(IC2B--IN)") (class "Default")
      (node (ref "IC2") (pin "6") (pinfunction "-IN_6") (pintype "input"))
      (node (ref "IC2") (pin "7") (pinfunction "OUT_7") (pintype "output"))
      (node (ref "R3") (pin "1") (pinfunction "1_1") (pintype "passive"))
      (node (ref "R4") (pin "1") (pinfunction "1_1") (pintype "passive"))
      (node (ref "R8") (pin "1") (pinfunction "1_1") (pintype "passive"))
    )
    (net (code "20") (name "Net-(IC2C--IN)") (class "Default")
      (node (ref "C8") (pin "2") (pinfunction "2_2") (pintype "passive"))
      (node (ref "IC2") (pin "9") (pinfunction "-IN_9") (pintype "input"))
      (node (ref "R10") (pin "1") (pinfunction "1_1") (pintype "passive"))
      (node (ref "R3") (pin "2") (pinfunction "2_2") (pintype "passive"))
    )
    (net (code "21") (name "Net-(IC2C-OUT)") (class "Default")
      (node (ref "C8") (pin "1") (pinfunction "1_1") (pintype "passive"))
      (node (ref "IC2") (pin "8") (pinfunction "OUT_8") (pintype "output"))
      (node (ref "R10") (pin "2") (pinfunction "2_2") (pintype "passive"))
      (node (ref "T2") (pin "2") (pinfunction "B_2") (pintype "passive"))
    )
    (net (code "22") (name "Net-(IC2D--IN)") (class "Default")
      (node (ref "C9") (pin "2") (pinfunction "2_2") (pintype "passive"))
      (node (ref "IC2") (pin "13") (pinfunction "-IN_13") (pintype "input"))
      (node (ref "R11") (pin "1") (pinfunction "1_1") (pintype "passive"))
      (node (ref "T2") (pin "6") (pinfunction "C_6") (pintype "passive"))
    )
    (net (code "23") (name "Net-(IC2D-OUT)") (class "Default")
      (node (ref "C9") (pin "1") (pinfunction "1_1") (pintype "passive"))
      (node (ref "IC2") (pin "14") (pinfunction "OUT_14") (pintype "output"))
      (node (ref "R12") (pin "1") (pinfunction "1_1") (pintype "passive"))
      (node (ref "VR2") (pin "1") (pinfunction "A_1") (pintype "passive"))
    )
    (net (code "24") (name "Net-(IC4A--IN)") (class "Default")
      (node (ref "IC4") (pin "2") (pinfunction "-IN_2") (pintype "input"))
      (node (ref "R50") (pin "2") (pinfunction "2_2") (pintype "passive"))
      (node (ref "R51") (pin "2") (pinfunction "2_2") (pintype "passive"))
      (node (ref "R52") (pin "1") (pinfunction "1_1") (pintype "passive"))
      (node (ref "R53") (pin "2") (pinfunction "2_2") (pintype "passive"))
    )
    (net (code "25") (name "Net-(IC4A-OUT)") (class "Default")
      (node (ref "IC4") (pin "1") (pinfunction "OUT_1") (pintype "output"))
      (node (ref "R49") (pin "1") (pinfunction "1_1") (pintype "passive"))
      (node (ref "R52") (pin "2") (pinfunction "2_2") (pintype "passive"))
    )
    (net (code "26") (name "Net-(IC4B--IN)") (class "Default")
      (node (ref "IC4") (pin "6") (pinfunction "-IN_6") (pintype "input"))
      (node (ref "R48") (pin "1") (pinfunction "1_1") (pintype "passive"))
      (node (ref "R49") (pin "2") (pinfunction "2_2") (pintype "passive"))
    )
    (net (code "27") (name "Net-(IC4B-OUT)") (class "Default")
      (node (ref "IC4") (pin "7") (pinfunction "OUT_7") (pintype "output"))
      (node (ref "R47") (pin "2") (pinfunction "2_2") (pintype "passive"))
      (node (ref "R48") (pin "2") (pinfunction "2_2") (pintype "passive"))
    )
    (net (code "28") (name "Net-(IC5A--IN)") (class "Default")
      (node (ref "D4") (pin "C") (pinfunction "C_C") (pintype "passive"))
      (node (ref "IC5") (pin "2") (pinfunction "-IN_2") (pintype "input"))
      (node (ref "R27") (pin "2") (pinfunction "2_2") (pintype "passive"))
      (node (ref "R28") (pin "1") (pinfunction "1_1") (pintype "passive"))
      (node (ref "R30") (pin "1") (pinfunction "1_1") (pintype "passive"))
    )
    (net (code "29") (name "Net-(IC5A-OUT)") (class "Default")
      (node (ref "D4") (pin "A") (pinfunction "A_A") (pintype "passive"))
      (node (ref "IC5") (pin "1") (pinfunction "OUT_1") (pintype "output"))
      (node (ref "R28") (pin "2") (pinfunction "2_2") (pintype "passive"))
      (node (ref "R29") (pin "1") (pinfunction "1_1") (pintype "passive"))
      (node (ref "T4") (pin "B") (pinfunction "B_B") (pintype "passive"))
      (node (ref "T4") (pin "C") (pinfunction "C_C") (pintype "passive"))
    )
    (net (code "30") (name "Net-(IC5B-+IN)") (class "Default")
      (node (ref "IC5") (pin "5") (pinfunction "+IN_5") (pintype "input"))
      (node (ref "R24") (pin "2") (pinfunction "2_2") (pintype "passive"))
      (node (ref "R25") (pin "1") (pinfunction "1_1") (pintype "passive"))
    )
    (net (code "31") (name "Net-(IC5B--IN)") (class "Default")
      (node (ref "IC5") (pin "6") (pinfunction "-IN_6") (pintype "input"))
      (node (ref "IC5") (pin "7") (pinfunction "OUT_7") (pintype "output"))
      (node (ref "R26") (pin "1") (pinfunction "1_1") (pintype "passive"))
      (node (ref "R27") (pin "1") (pinfunction "1_1") (pintype "passive"))
      (node (ref "R31") (pin "1") (pinfunction "1_1") (pintype "passive"))
    )
    (net (code "32") (name "Net-(IC5C--IN)") (class "Default")
      (node (ref "C12") (pin "2") (pinfunction "2_2") (pintype "passive"))
      (node (ref "IC5") (pin "9") (pinfunction "-IN_9") (pintype "input"))
      (node (ref "R26") (pin "2") (pinfunction "2_2") (pintype "passive"))
      (node (ref "R33") (pin "1") (pinfunction "1_1") (pintype "passive"))
    )
    (net (code "33") (name "Net-(IC5C-OUT)") (class "Default")
      (node (ref "C12") (pin "1") (pinfunction "1_1") (pintype "passive"))
      (node (ref "IC5") (pin "8") (pinfunction "OUT_8") (pintype "output"))
      (node (ref "R33") (pin "2") (pinfunction "2_2") (pintype "passive"))
      (node (ref "T5") (pin "2") (pinfunction "B_2") (pintype "passive"))
    )
    (net (code "34") (name "Net-(IC5D--IN)") (class "Default")
      (node (ref "C13") (pin "2") (pinfunction "2_2") (pintype "passive"))
      (node (ref "IC5") (pin "13") (pinfunction "-IN_13") (pintype "input"))
      (node (ref "R34") (pin "1") (pinfunction "1_1") (pintype "passive"))
      (node (ref "T5") (pin "6") (pinfunction "C_6") (pintype "passive"))
    )
    (net (code "35") (name "Net-(IC5D-OUT)") (class "Default")
      (node (ref "C13") (pin "1") (pinfunction "1_1") (pintype "passive"))
      (node (ref "IC5") (pin "14") (pinfunction "OUT_14") (pintype "output"))
      (node (ref "R35") (pin "1") (pinfunction "1_1") (pintype "passive"))
      (node (ref "VR4") (pin "1") (pinfunction "A_1") (pintype "passive"))
    )
    (net (code "36") (name "Net-(R7-Pad2)") (class "Default")
      (node (ref "R7") (pin "2") (pinfunction "2_2") (pintype "passive"))
      (node (ref "T1") (pin "E") (pinfunction "E_E") (pintype "passive"))
    )
    (net (code "37") (name "Net-(R18-S)") (class "Default")
      (node (ref "R17") (pin "1") (pinfunction "1_1") (pintype "passive"))
      (node (ref "R18") (pin "2") (pinfunction "S_2") (pintype "passive"))
    )
    (net (code "38") (name "Net-(R22-Pad1)") (class "Default")
      (node (ref "R22") (pin "1") (pinfunction "1_1") (pintype "passive"))
      (node (ref "R23") (pin "2") (pinfunction "2_2") (pintype "passive"))
      (node (ref "T3") (pin "C") (pinfunction "C_C") (pintype "passive"))
    )
    (net (code "39") (name "Net-(R30-Pad2)") (class "Default")
      (node (ref "R30") (pin "2") (pinfunction "2_2") (pintype "passive"))
      (node (ref "T4") (pin "E") (pinfunction "E_E") (pintype "passive"))
    )
    (net (code "40") (name "Net-(R41-S)") (class "Default")
      (node (ref "R40") (pin "1") (pinfunction "1_1") (pintype "passive"))
      (node (ref "R41") (pin "2") (pinfunction "S_2") (pintype "passive"))
    )
    (net (code "41") (name "Net-(R45-Pad1)") (class "Default")
      (node (ref "R45") (pin "1") (pinfunction "1_1") (pintype "passive"))
      (node (ref "R46") (pin "2") (pinfunction "2_2") (pintype "passive"))
      (node (ref "T6") (pin "C") (pinfunction "C_C") (pintype "passive"))
    )
    (net (code "42") (name "Net-(T2A-E)") (class "Default")
      (node (ref "R12") (pin "2") (pinfunction "2_2") (pintype "passive"))
      (node (ref "T2") (pin "1") (pinfunction "E_1") (pintype "passive"))
      (node (ref "T2") (pin "4") (pinfunction "E_4") (pintype "passive"))
    )
    (net (code "43") (name "Net-(T5A-E)") (class "Default")
      (node (ref "R35") (pin "2") (pinfunction "2_2") (pintype "passive"))
      (node (ref "T5") (pin "1") (pinfunction "E_1") (pintype "passive"))
      (node (ref "T5") (pin "4") (pinfunction "E_4") (pintype "passive"))
    )
    (net (code "44") (name "Net-(U$1-2)") (class "Default")
      (node (ref "R1") (pin "1") (pinfunction "1_1") (pintype "passive"))
      (node (ref "U$1") (pin "P$1_TIP") (pinfunction "2_P$1_TIP") (pintype "passive"))
    )
    (net (code "45") (name "Net-(U$1-3)") (class "Default")
      (node (ref "SJ3") (pin "2") (pinfunction "2_2") (pintype "passive"))
      (node (ref "U$1") (pin "P$2_SWITCH") (pinfunction "3_P$2_SWITCH") (pintype "passive"))
    )
    (net (code "46") (name "Net-(U$2-2)") (class "Default")
      (node (ref "R53") (pin "1") (pinfunction "1_1") (pintype "passive"))
      (node (ref "U$2") (pin "P$1_TIP") (pinfunction "2_P$1_TIP") (pintype "passive"))
    )
    (net (code "47") (name "Net-(U$3-2)") (class "Default")
      (node (ref "R13") (pin "1") (pinfunction "1_1") (pintype "passive"))
      (node (ref "U$3") (pin "P$1_TIP") (pinfunction "2_P$1_TIP") (pintype "passive"))
    )
    (net (code "48") (name "Net-(U$4-2)") (class "Default")
      (node (ref "R21") (pin "1") (pinfunction "1_1") (pintype "passive"))
      (node (ref "SJ1") (pin "2") (pinfunction "2_2") (pintype "passive"))
      (node (ref "U$4") (pin "P$1_TIP") (pinfunction "2_P$1_TIP") (pintype "passive"))
    )
    (net (code "49") (name "Net-(U$6-2)") (class "Default")
      (node (ref "R24") (pin "1") (pinfunction "1_1") (pintype "passive"))
      (node (ref "U$6") (pin "P$1_TIP") (pinfunction "2_P$1_TIP") (pintype "passive"))
    )
    (net (code "50") (name "Net-(U$6-3)") (class "Default")
      (node (ref "SJ4") (pin "2") (pinfunction "2_2") (pintype "passive"))
      (node (ref "U$6") (pin "P$2_SWITCH") (pinfunction "3_P$2_SWITCH") (pintype "passive"))
    )
    (net (code "51") (name "Net-(U$7-2)") (class "Default")
      (node (ref "R36") (pin "1") (pinfunction "1_1") (pintype "passive"))
      (node (ref "U$7") (pin "P$1_TIP") (pinfunction "2_P$1_TIP") (pintype "passive"))
    )
    (net (code "52") (name "Net-(U$8-2)") (class "Default")
      (node (ref "R44") (pin "1") (pinfunction "1_1") (pintype "passive"))
      (node (ref "SJ2") (pin "2") (pinfunction "2_2") (pintype "passive"))
      (node (ref "U$8") (pin "P$1_TIP") (pinfunction "2_P$1_TIP") (pintype "passive"))
    )
    (net (code "53") (name "Net-(U$9-2)") (class "Default")
      (node (ref "R47") (pin "1") (pinfunction "1_1") (pintype "passive"))
      (node (ref "U$9") (pin "P$1_TIP") (pinfunction "2_P$1_TIP") (pintype "passive"))
    )
    (net (code "54") (name "Net-(U1A-+IN)") (class "Default")
      (node (ref "U1") (pin "3") (pinfunction "+IN_3") (pintype "input"))
      (node (ref "VR2") (pin "2") (pinfunction "S_2") (pintype "passive"))
    )
    (net (code "55") (name "Net-(U1A--IN)") (class "Default")
      (node (ref "T3") (pin "B") (pinfunction "B_B") (pintype "passive"))
      (node (ref "U1") (pin "1") (pinfunction "OUT_1") (pintype "output"))
      (node (ref "U1") (pin "2") (pinfunction "-IN_2") (pintype "input"))
    )
    (net (code "56") (name "Net-(U1B-+IN)") (class "Default")
      (node (ref "U1") (pin "5") (pinfunction "+IN_5") (pintype "input"))
      (node (ref "VR1") (pin "2") (pinfunction "S_2") (pintype "passive"))
    )
    (net (code "57") (name "Net-(U1B--IN)") (class "Default")
      (node (ref "C11") (pin "2") (pinfunction "2_2") (pintype "passive"))
      (node (ref "R19") (pin "2") (pinfunction "2_2") (pintype "passive"))
      (node (ref "R20") (pin "1") (pinfunction "1_1") (pintype "passive"))
      (node (ref "U1") (pin "6") (pinfunction "-IN_6") (pintype "input"))
    )
    (net (code "58") (name "Net-(U1B-OUT)") (class "Default")
      (node (ref "C11") (pin "1") (pinfunction "1_1") (pintype "passive"))
      (node (ref "R19") (pin "1") (pinfunction "1_1") (pintype "passive"))
      (node (ref "R21") (pin "2") (pinfunction "2_2") (pintype "passive"))
      (node (ref "U1") (pin "7") (pinfunction "OUT_7") (pintype "output"))
    )
    (net (code "59") (name "Net-(U2A-+IN)") (class "Default")
      (node (ref "U2") (pin "3") (pinfunction "+IN_3") (pintype "input"))
      (node (ref "VR4") (pin "2") (pinfunction "S_2") (pintype "passive"))
    )
    (net (code "60") (name "Net-(U2A--IN)") (class "Default")
      (node (ref "T6") (pin "B") (pinfunction "B_B") (pintype "passive"))
      (node (ref "U2") (pin "1") (pinfunction "OUT_1") (pintype "output"))
      (node (ref "U2") (pin "2") (pinfunction "-IN_2") (pintype "input"))
    )
    (net (code "61") (name "Net-(U2B-+IN)") (class "Default")
      (node (ref "U2") (pin "5") (pinfunction "+IN_5") (pintype "input"))
      (node (ref "VR3") (pin "2") (pinfunction "S_2") (pintype "passive"))
    )
    (net (code "62") (name "Net-(U2B--IN)") (class "Default")
      (node (ref "C15") (pin "2") (pinfunction "2_2") (pintype "passive"))
      (node (ref "R42") (pin "2") (pinfunction "2_2") (pintype "passive"))
      (node (ref "R43") (pin "1") (pinfunction "1_1") (pintype "passive"))
      (node (ref "U2") (pin "6") (pinfunction "-IN_6") (pintype "input"))
    )
    (net (code "63") (name "Net-(U2B-OUT)") (class "Default")
      (node (ref "C15") (pin "1") (pinfunction "1_1") (pintype "passive"))
      (node (ref "R42") (pin "1") (pinfunction "1_1") (pintype "passive"))
      (node (ref "R44") (pin "2") (pinfunction "2_2") (pintype "passive"))
      (node (ref "U2") (pin "7") (pinfunction "OUT_7") (pintype "output"))
    )
    (net (code "64") (name "Net-(VR2-E)") (class "Default")
      (node (ref "R6") (pin "2") (pinfunction "2_2") (pintype "passive"))
      (node (ref "R8") (pin "2") (pinfunction "2_2") (pintype "passive"))
      (node (ref "R9") (pin "2") (pinfunction "2_2") (pintype "passive"))
      (node (ref "VR2") (pin "3") (pinfunction "E_3") (pintype "passive"))
    )
    (net (code "65") (name "Net-(VR4-E)") (class "Default")
      (node (ref "R29") (pin "2") (pinfunction "2_2") (pintype "passive"))
      (node (ref "R31") (pin "2") (pinfunction "2_2") (pintype "passive"))
      (node (ref "R32") (pin "2") (pinfunction "2_2") (pintype "passive"))
      (node (ref "VR4") (pin "3") (pinfunction "E_3") (pintype "passive"))
    )
    (net (code "66") (name "REF_10") (class "Default")
      (node (ref "R54") (pin "1") (pinfunction "1_1") (pintype "passive"))
      (node (ref "R55") (pin "2") (pinfunction "2_2") (pintype "passive"))
      (node (ref "SJ3") (pin "1") (pinfunction "1_1") (pintype "passive"))
      (node (ref "SJ4") (pin "1") (pinfunction "1_1") (pintype "passive"))
    )
    (net (code "67") (name "unconnected-(IC1C-I_DIODE-Pad2)") (class "Default")
      (node (ref "IC1") (pin "2") (pinfunction "I_DIODE_2") (pintype "input"))
    )
    (net (code "68") (name "unconnected-(IC1D-I_DIODE-Pad15)") (class "Default")
      (node (ref "IC1") (pin "15") (pinfunction "I_DIODE_15") (pintype "input"))
    )
    (net (code "69") (name "unconnected-(U$2-3-PadP$2_SWITCH)") (class "Default")
      (node (ref "U$2") (pin "P$2_SWITCH") (pinfunction "3_P$2_SWITCH") (pintype "passive"))
    )
    (net (code "70") (name "unconnected-(U$3-3-PadP$2_SWITCH)") (class "Default")
      (node (ref "U$3") (pin "P$2_SWITCH") (pinfunction "3_P$2_SWITCH") (pintype "passive"))
    )
    (net (code "71") (name "unconnected-(U$7-3-PadP$2_SWITCH)") (class "Default")
      (node (ref "U$7") (pin "P$2_SWITCH") (pinfunction "3_P$2_SWITCH") (pintype "passive"))
    )
    (net (code "72") (name "unconnected-(U$9-3-PadP$2_SWITCH)") (class "Default")
      (node (ref "U$9") (pin "P$2_SWITCH") (pinfunction "3_P$2_SWITCH") (pintype "passive"))
    )
  )
)
